# propdev.net
KiCad netlist of a schematic drawn in EAGLE
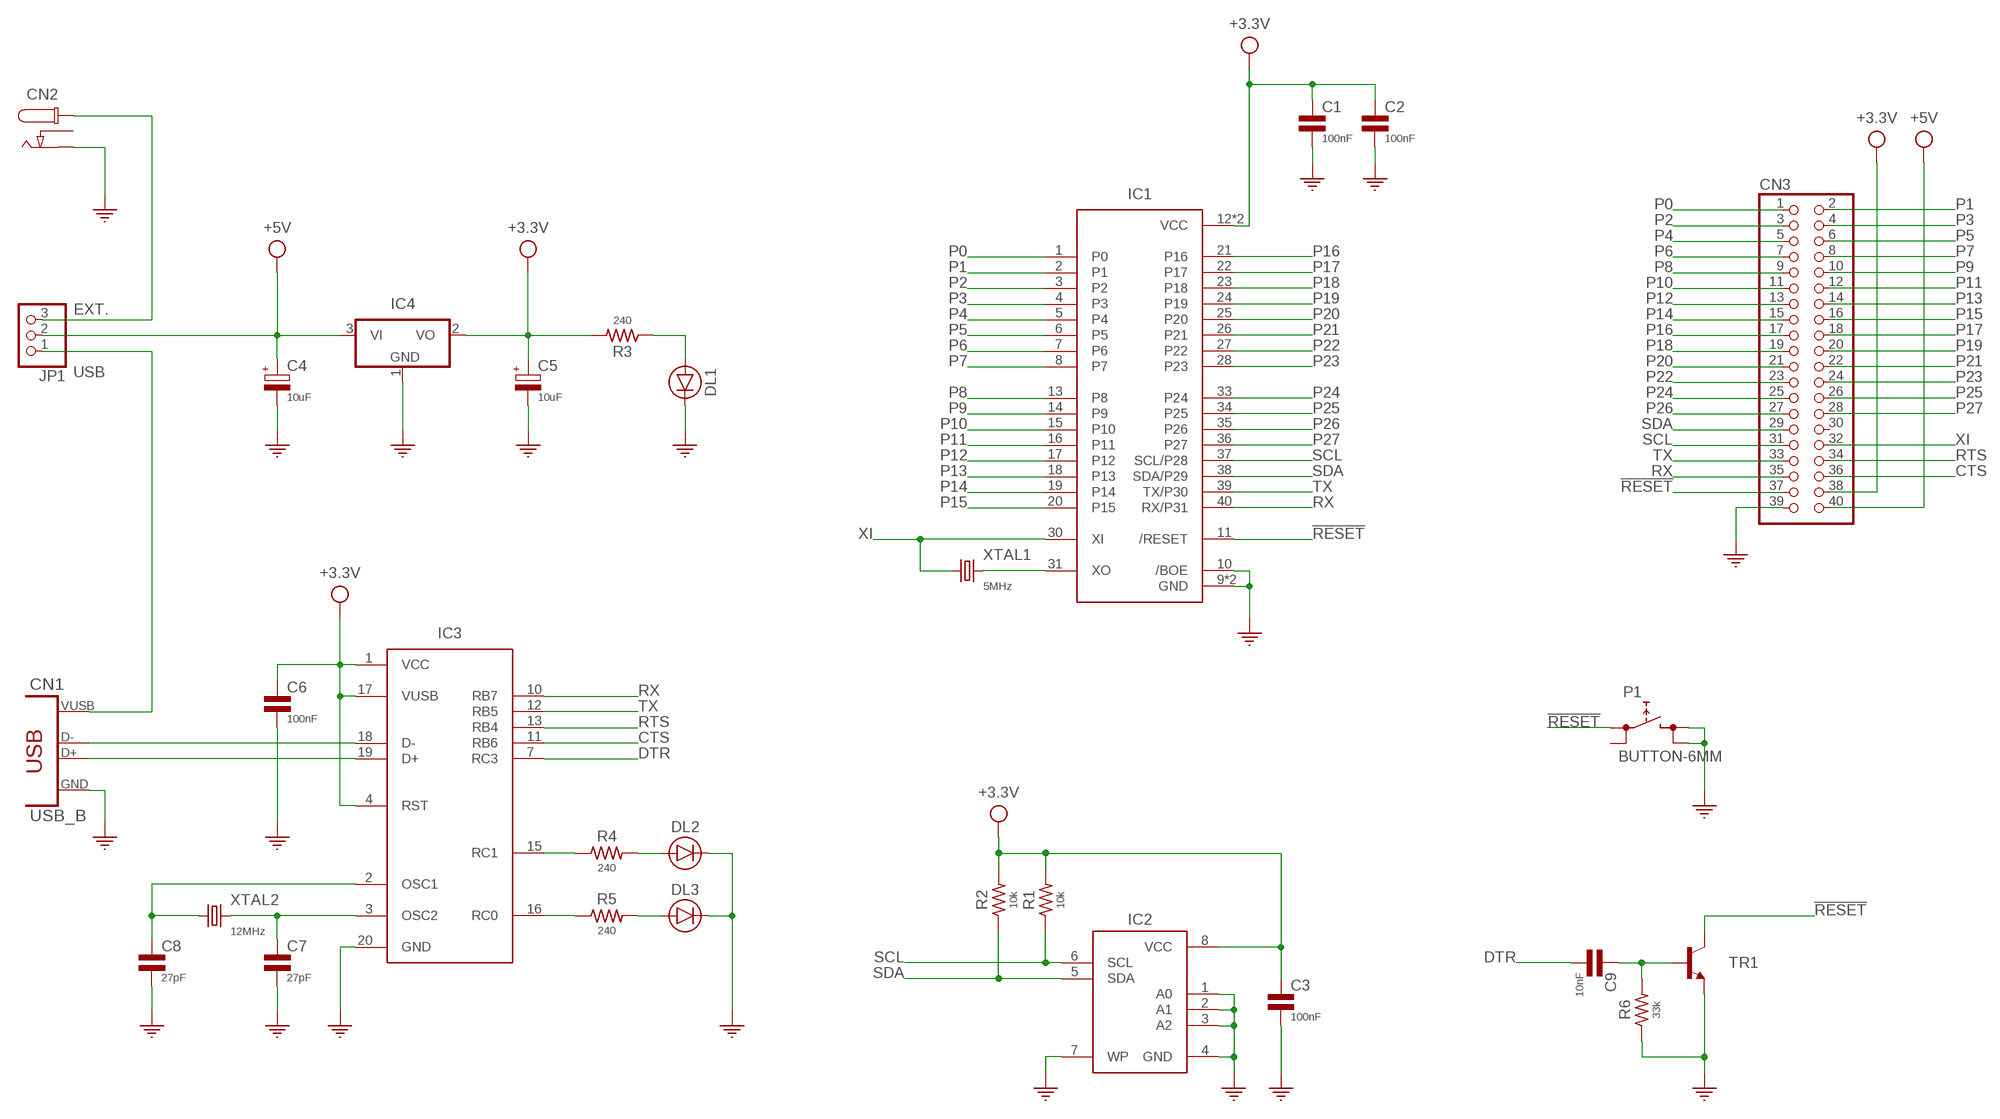
[diagram p0: schematic, sheet 1]

(export (version "E")
  (design (tool "Eeschema 10.0.6"))
  (components
    (comp (ref "C1")
      (value "100nF")
      (footprint "eagle-import:C050-025X075")
      (libsource (lib "eagle-import") (part "C"))
    )
    (comp (ref "C2")
      (value "100nF")
      (footprint "eagle-import:C050-025X075")
      (libsource (lib "eagle-import") (part "C"))
    )
    (comp (ref "C3")
      (value "100nF")
      (footprint "eagle-import:C050-025X075")
      (libsource (lib "eagle-import") (part "C"))
    )
    (comp (ref "C4")
      (value "10uF")
      (footprint "eagle-import:E2,5-6")
      (libsource (lib "eagle-import") (part "CP-2.5-6"))
    )
    (comp (ref "C5")
      (value "10uF")
      (footprint "eagle-import:E2,5-6")
      (libsource (lib "eagle-import") (part "CP-2.5-6"))
    )
    (comp (ref "C6")
      (value "100nF")
      (footprint "eagle-import:C050-025X075")
      (libsource (lib "eagle-import") (part "C"))
    )
    (comp (ref "C7")
      (value "27pF")
      (footprint "eagle-import:C050-025X075")
      (libsource (lib "eagle-import") (part "C"))
    )
    (comp (ref "C8")
      (value "27pF")
      (footprint "eagle-import:C050-025X075")
      (libsource (lib "eagle-import") (part "C"))
    )
    (comp (ref "C9")
      (value "10nF")
      (footprint "eagle-import:C050-025X075")
      (libsource (lib "eagle-import") (part "C"))
    )
    (comp (ref "CN1")
      (value "USB_B")
      (footprint "eagle-import:USB-B")
      (libsource (lib "eagle-import") (part "USB_B"))
    )
    (comp (ref "CN2")
      (value "DC_JACK")
      (footprint "eagle-import:PJ-102A")
      (libsource (lib "eagle-import") (part "DC_JACK"))
    )
    (comp (ref "CN3")
      (value "PINHD-2X20B")
      (footprint "eagle-import:2X20B")
      (libsource (lib "eagle-import") (part "PINHD-2X20B"))
    )
    (comp (ref "DL1")
      (value "LED-3MM")
      (footprint "eagle-import:LED3MM")
      (libsource (lib "eagle-import") (part "LED-3MM"))
    )
    (comp (ref "DL2")
      (value "LED-3MM")
      (footprint "eagle-import:LED3MM")
      (libsource (lib "eagle-import") (part "LED-3MM"))
    )
    (comp (ref "DL3")
      (value "LED-3MM")
      (footprint "eagle-import:LED3MM")
      (libsource (lib "eagle-import") (part "LED-3MM"))
    )
    (comp (ref "IC1")
      (value "P8X32A")
      (footprint "eagle-import:DIL40")
      (libsource (lib "eagle-import") (part "P8X32A"))
    )
    (comp (ref "IC2")
      (value "24LC512-I/P")
      (footprint "eagle-import:DIL08")
      (libsource (lib "eagle-import") (part "24LC-I/P512"))
    )
    (comp (ref "IC3")
      (value "PIC18F14K50-I/P")
      (footprint "eagle-import:DIL20")
      (libsource (lib "eagle-import") (part "PIC18F14K50-I/P"))
    )
    (comp (ref "IC4")
      (value "LM1117T-3.3")
      (footprint "eagle-import:TO220H")
      (libsource (lib "eagle-import") (part "LM1117T"))
    )
    (comp (ref "JP1")
      (value "PINHD-1X3")
      (footprint "eagle-import:1X03")
      (libsource (lib "eagle-import") (part "PINHD-1X3"))
    )
    (comp (ref "P1")
      (value "BUTTON-6MM")
      (footprint "eagle-import:TL1105")
      (libsource (lib "eagle-import") (part "BUTTON-6MM"))
    )
    (comp (ref "R1")
      (value "10k")
      (footprint "eagle-import:0207_10")
      (libsource (lib "eagle-import") (part "R-1/4W"))
    )
    (comp (ref "R2")
      (value "10k")
      (footprint "eagle-import:0207_10")
      (libsource (lib "eagle-import") (part "R-1/4W"))
    )
    (comp (ref "R3")
      (value "240")
      (footprint "eagle-import:0207_10")
      (libsource (lib "eagle-import") (part "R-1/4W"))
    )
    (comp (ref "R4")
      (value "240")
      (footprint "eagle-import:0207_10")
      (libsource (lib "eagle-import") (part "R-1/4W"))
    )
    (comp (ref "R5")
      (value "240")
      (footprint "eagle-import:0207_10")
      (libsource (lib "eagle-import") (part "R-1/4W"))
    )
    (comp (ref "R6")
      (value "33k")
      (footprint "eagle-import:0207_10")
      (libsource (lib "eagle-import") (part "R-1/4W"))
    )
    (comp (ref "TR1")
      (value "BC547")
      (footprint "eagle-import:TO92")
      (libsource (lib "eagle-import") (part "BC547"))
    )
    (comp (ref "XTAL1")
      (value "5MHz")
      (footprint "eagle-import:HC49_S")
      (libsource (lib "eagle-import") (part "CRYSTAL-HC49/S"))
    )
    (comp (ref "XTAL2")
      (value "12MHz")
      (footprint "eagle-import:HC49_S")
      (libsource (lib "eagle-import") (part "CRYSTAL-HC49/S"))
    )
  )
  (nets
    (net (code "1") (name "+3.3V") (class "Default")
      (node (ref "C1") (pin "1") (pinfunction "1_1") (pintype "passive"))
      (node (ref "C2") (pin "1") (pinfunction "1_1") (pintype "passive"))
      (node (ref "C3") (pin "1") (pinfunction "1_1") (pintype "passive"))
      (node (ref "C5") (pin "+") (pinfunction "+_+") (pintype "passive"))
      (node (ref "C6") (pin "1") (pinfunction "1_1") (pintype "passive"))
      (node (ref "CN3") (pin "38") (pinfunction "38_38") (pintype "passive"))
      (node (ref "IC1") (pin "12") (pinfunction "VCC_12") (pintype "bidirectional"))
      (node (ref "IC1") (pin "32") (pinfunction "VCC_32") (pintype "bidirectional"))
      (node (ref "IC2") (pin "8") (pinfunction "VCC_8") (pintype "bidirectional"))
      (node (ref "IC3") (pin "1") (pinfunction "VCC_1") (pintype "power_in"))
      (node (ref "IC3") (pin "17") (pinfunction "VUSB_17") (pintype "bidirectional"))
      (node (ref "IC3") (pin "4") (pinfunction "RST_4") (pintype "bidirectional"))
      (node (ref "IC4") (pin "2") (pinfunction "VO_2") (pintype "passive"))
      (node (ref "R1") (pin "2") (pinfunction "2_2") (pintype "passive"))
      (node (ref "R2") (pin "2") (pinfunction "2_2") (pintype "passive"))
      (node (ref "R3") (pin "2") (pinfunction "2_2") (pintype "passive"))
    )
    (net (code "2") (name "+5V") (class "Default")
      (node (ref "C4") (pin "+") (pinfunction "+_+") (pintype "passive"))
      (node (ref "CN3") (pin "40") (pinfunction "40_40") (pintype "passive"))
      (node (ref "IC4") (pin "3") (pinfunction "VI_3") (pintype "input"))
      (node (ref "JP1") (pin "2") (pinfunction "2_2") (pintype "passive"))
    )
    (net (code "3") (name "/CTS") (class "Default")
      (node (ref "CN3") (pin "36") (pinfunction "36_36") (pintype "passive"))
      (node (ref "IC3") (pin "11") (pinfunction "RB6_11") (pintype "bidirectional"))
    )
    (net (code "4") (name "/DTR") (class "Default")
      (node (ref "C9") (pin "2") (pinfunction "2_2") (pintype "passive"))
      (node (ref "IC3") (pin "7") (pinfunction "RC3_7") (pintype "bidirectional"))
    )
    (net (code "5") (name "/EXT.") (class "Default")
      (node (ref "CN2") (pin "P1") (pinfunction "P1_P1") (pintype "passive"))
      (node (ref "JP1") (pin "3") (pinfunction "3_3") (pintype "passive"))
    )
    (net (code "6") (name "/P0") (class "Default")
      (node (ref "CN3") (pin "1") (pinfunction "1_1") (pintype "passive"))
      (node (ref "IC1") (pin "1") (pinfunction "P0_1") (pintype "bidirectional"))
    )
    (net (code "7") (name "/P1") (class "Default")
      (node (ref "CN3") (pin "2") (pinfunction "2_2") (pintype "passive"))
      (node (ref "IC1") (pin "2") (pinfunction "P1_2") (pintype "bidirectional"))
    )
    (net (code "8") (name "/P2") (class "Default")
      (node (ref "CN3") (pin "3") (pinfunction "3_3") (pintype "passive"))
      (node (ref "IC1") (pin "3") (pinfunction "P2_3") (pintype "bidirectional"))
    )
    (net (code "9") (name "/P3") (class "Default")
      (node (ref "CN3") (pin "4") (pinfunction "4_4") (pintype "passive"))
      (node (ref "IC1") (pin "4") (pinfunction "P3_4") (pintype "bidirectional"))
    )
    (net (code "10") (name "/P4") (class "Default")
      (node (ref "CN3") (pin "5") (pinfunction "5_5") (pintype "passive"))
      (node (ref "IC1") (pin "5") (pinfunction "P4_5") (pintype "bidirectional"))
    )
    (net (code "11") (name "/P5") (class "Default")
      (node (ref "CN3") (pin "6") (pinfunction "6_6") (pintype "passive"))
      (node (ref "IC1") (pin "6") (pinfunction "P5_6") (pintype "bidirectional"))
    )
    (net (code "12") (name "/P6") (class "Default")
      (node (ref "CN3") (pin "7") (pinfunction "7_7") (pintype "passive"))
      (node (ref "IC1") (pin "7") (pinfunction "P6_7") (pintype "bidirectional"))
    )
    (net (code "13") (name "/P7") (class "Default")
      (node (ref "CN3") (pin "8") (pinfunction "8_8") (pintype "passive"))
      (node (ref "IC1") (pin "8") (pinfunction "P7_8") (pintype "bidirectional"))
    )
    (net (code "14") (name "/P8") (class "Default")
      (node (ref "CN3") (pin "9") (pinfunction "9_9") (pintype "passive"))
      (node (ref "IC1") (pin "13") (pinfunction "P8_13") (pintype "bidirectional"))
    )
    (net (code "15") (name "/P9") (class "Default")
      (node (ref "CN3") (pin "10") (pinfunction "10_10") (pintype "passive"))
      (node (ref "IC1") (pin "14") (pinfunction "P9_14") (pintype "bidirectional"))
    )
    (net (code "16") (name "/P10") (class "Default")
      (node (ref "CN3") (pin "11") (pinfunction "11_11") (pintype "passive"))
      (node (ref "IC1") (pin "15") (pinfunction "P10_15") (pintype "bidirectional"))
    )
    (net (code "17") (name "/P11") (class "Default")
      (node (ref "CN3") (pin "12") (pinfunction "12_12") (pintype "passive"))
      (node (ref "IC1") (pin "16") (pinfunction "P11_16") (pintype "bidirectional"))
    )
    (net (code "18") (name "/P12") (class "Default")
      (node (ref "CN3") (pin "13") (pinfunction "13_13") (pintype "passive"))
      (node (ref "IC1") (pin "17") (pinfunction "P12_17") (pintype "bidirectional"))
    )
    (net (code "19") (name "/P13") (class "Default")
      (node (ref "CN3") (pin "14") (pinfunction "14_14") (pintype "passive"))
      (node (ref "IC1") (pin "18") (pinfunction "P13_18") (pintype "bidirectional"))
    )
    (net (code "20") (name "/P14") (class "Default")
      (node (ref "CN3") (pin "15") (pinfunction "15_15") (pintype "passive"))
      (node (ref "IC1") (pin "19") (pinfunction "P14_19") (pintype "bidirectional"))
    )
    (net (code "21") (name "/P15") (class "Default")
      (node (ref "CN3") (pin "16") (pinfunction "16_16") (pintype "passive"))
      (node (ref "IC1") (pin "20") (pinfunction "P15_20") (pintype "bidirectional"))
    )
    (net (code "22") (name "/P16") (class "Default")
      (node (ref "CN3") (pin "17") (pinfunction "17_17") (pintype "passive"))
      (node (ref "IC1") (pin "21") (pinfunction "P16_21") (pintype "bidirectional"))
    )
    (net (code "23") (name "/P17") (class "Default")
      (node (ref "CN3") (pin "18") (pinfunction "18_18") (pintype "passive"))
      (node (ref "IC1") (pin "22") (pinfunction "P17_22") (pintype "bidirectional"))
    )
    (net (code "24") (name "/P18") (class "Default")
      (node (ref "CN3") (pin "19") (pinfunction "19_19") (pintype "passive"))
      (node (ref "IC1") (pin "23") (pinfunction "P18_23") (pintype "bidirectional"))
    )
    (net (code "25") (name "/P19") (class "Default")
      (node (ref "CN3") (pin "20") (pinfunction "20_20") (pintype "passive"))
      (node (ref "IC1") (pin "24") (pinfunction "P19_24") (pintype "bidirectional"))
    )
    (net (code "26") (name "/P20") (class "Default")
      (node (ref "CN3") (pin "21") (pinfunction "21_21") (pintype "passive"))
      (node (ref "IC1") (pin "25") (pinfunction "P20_25") (pintype "bidirectional"))
    )
    (net (code "27") (name "/P21") (class "Default")
      (node (ref "CN3") (pin "22") (pinfunction "22_22") (pintype "passive"))
      (node (ref "IC1") (pin "26") (pinfunction "P21_26") (pintype "bidirectional"))
    )
    (net (code "28") (name "/P22") (class "Default")
      (node (ref "CN3") (pin "23") (pinfunction "23_23") (pintype "passive"))
      (node (ref "IC1") (pin "27") (pinfunction "P22_27") (pintype "bidirectional"))
    )
    (net (code "29") (name "/P23") (class "Default")
      (node (ref "CN3") (pin "24") (pinfunction "24_24") (pintype "passive"))
      (node (ref "IC1") (pin "28") (pinfunction "P23_28") (pintype "bidirectional"))
    )
    (net (code "30") (name "/P24") (class "Default")
      (node (ref "CN3") (pin "25") (pinfunction "25_25") (pintype "passive"))
      (node (ref "IC1") (pin "33") (pinfunction "P24_33") (pintype "bidirectional"))
    )
    (net (code "31") (name "/P25") (class "Default")
      (node (ref "CN3") (pin "26") (pinfunction "26_26") (pintype "passive"))
      (node (ref "IC1") (pin "34") (pinfunction "P25_34") (pintype "bidirectional"))
    )
    (net (code "32") (name "/P26") (class "Default")
      (node (ref "CN3") (pin "27") (pinfunction "27_27") (pintype "passive"))
      (node (ref "IC1") (pin "35") (pinfunction "P26_35") (pintype "bidirectional"))
    )
    (net (code "33") (name "/P27") (class "Default")
      (node (ref "CN3") (pin "28") (pinfunction "28_28") (pintype "passive"))
      (node (ref "IC1") (pin "36") (pinfunction "P27_36") (pintype "bidirectional"))
    )
    (net (code "34") (name "/RTS") (class "Default")
      (node (ref "CN3") (pin "34") (pinfunction "34_34") (pintype "passive"))
      (node (ref "IC3") (pin "13") (pinfunction "RB4_13") (pintype "bidirectional"))
    )
    (net (code "35") (name "/RX") (class "Default")
      (node (ref "CN3") (pin "35") (pinfunction "35_35") (pintype "passive"))
      (node (ref "IC1") (pin "40") (pinfunction "RX/P31_40") (pintype "bidirectional"))
      (node (ref "IC3") (pin "10") (pinfunction "RB7_10") (pintype "bidirectional"))
    )
    (net (code "36") (name "/SCL") (class "Default")
      (node (ref "CN3") (pin "31") (pinfunction "31_31") (pintype "passive"))
      (node (ref "IC1") (pin "37") (pinfunction "SCL/P28_37") (pintype "bidirectional"))
      (node (ref "IC2") (pin "6") (pinfunction "SCL_6") (pintype "bidirectional"))
      (node (ref "R1") (pin "1") (pinfunction "1_1") (pintype "passive"))
    )
    (net (code "37") (name "/SDA") (class "Default")
      (node (ref "CN3") (pin "29") (pinfunction "29_29") (pintype "passive"))
      (node (ref "IC1") (pin "38") (pinfunction "SDA/P29_38") (pintype "bidirectional"))
      (node (ref "IC2") (pin "5") (pinfunction "SDA_5") (pintype "bidirectional"))
      (node (ref "R2") (pin "1") (pinfunction "1_1") (pintype "passive"))
    )
    (net (code "38") (name "/TX") (class "Default")
      (node (ref "CN3") (pin "33") (pinfunction "33_33") (pintype "passive"))
      (node (ref "IC1") (pin "39") (pinfunction "TX/P30_39") (pintype "bidirectional"))
      (node (ref "IC3") (pin "12") (pinfunction "RB5_12") (pintype "bidirectional"))
    )
    (net (code "39") (name "/USB") (class "Default")
      (node (ref "CN1") (pin "1") (pinfunction "VUSB_1") (pintype "power_in"))
      (node (ref "JP1") (pin "1") (pinfunction "1_1") (pintype "passive"))
    )
    (net (code "40") (name "/XI") (class "Default")
      (node (ref "CN3") (pin "32") (pinfunction "32_32") (pintype "passive"))
      (node (ref "IC1") (pin "30") (pinfunction "XI_30") (pintype "open_collector"))
      (node (ref "XTAL1") (pin "1") (pinfunction "1_1") (pintype "passive"))
    )
    (net (code "41") (name "/~{RESET}") (class "Default")
      (node (ref "CN3") (pin "37") (pinfunction "37_37") (pintype "passive"))
      (node (ref "IC1") (pin "11") (pinfunction "/RESET_11") (pintype "bidirectional"))
      (node (ref "P1") (pin "1") (pinfunction "0_1") (pintype "passive"))
      (node (ref "TR1") (pin "3") (pinfunction "C_3") (pintype "passive"))
    )
    (net (code "42") (name "GND") (class "Default")
      (node (ref "C1") (pin "2") (pinfunction "2_2") (pintype "passive"))
      (node (ref "C2") (pin "2") (pinfunction "2_2") (pintype "passive"))
      (node (ref "C3") (pin "2") (pinfunction "2_2") (pintype "passive"))
      (node (ref "C4") (pin "-") (pinfunction "-_-") (pintype "passive"))
      (node (ref "C5") (pin "-") (pinfunction "-_-") (pintype "passive"))
      (node (ref "C6") (pin "2") (pinfunction "2_2") (pintype "passive"))
      (node (ref "C7") (pin "2") (pinfunction "2_2") (pintype "passive"))
      (node (ref "C8") (pin "2") (pinfunction "2_2") (pintype "passive"))
      (node (ref "CN1") (pin "4") (pinfunction "GND_4") (pintype "power_in"))
      (node (ref "CN2") (pin "P3") (pinfunction "P2_P3") (pintype "passive"))
      (node (ref "CN3") (pin "39") (pinfunction "39_39") (pintype "passive"))
      (node (ref "DL1") (pin "K") (pinfunction "C_K") (pintype "passive"))
      (node (ref "DL2") (pin "K") (pinfunction "C_K") (pintype "passive"))
      (node (ref "DL3") (pin "K") (pinfunction "C_K") (pintype "passive"))
      (node (ref "IC1") (pin "10") (pinfunction "/BOE_10") (pintype "input"))
      (node (ref "IC1") (pin "29") (pinfunction "GND_29") (pintype "bidirectional"))
      (node (ref "IC1") (pin "9") (pinfunction "GND_9") (pintype "bidirectional"))
      (node (ref "IC2") (pin "1") (pinfunction "A0_1") (pintype "input"))
      (node (ref "IC2") (pin "2") (pinfunction "A1_2") (pintype "input"))
      (node (ref "IC2") (pin "3") (pinfunction "A2_3") (pintype "input"))
      (node (ref "IC2") (pin "4") (pinfunction "GND_4") (pintype "bidirectional"))
      (node (ref "IC2") (pin "7") (pinfunction "WP_7") (pintype "input"))
      (node (ref "IC3") (pin "20") (pinfunction "GND_20") (pintype "power_in"))
      (node (ref "IC4") (pin "1") (pinfunction "GND_1") (pintype "passive"))
      (node (ref "P1") (pin "2") (pinfunction "1_2") (pintype "passive"))
      (node (ref "P1") (pin "4") (pinfunction "1_4") (pintype "passive"))
      (node (ref "R6") (pin "1") (pinfunction "1_1") (pintype "passive"))
      (node (ref "TR1") (pin "1") (pinfunction "E_1") (pintype "passive"))
    )
    (net (code "43") (name "Net-(CN1-D+)") (class "Default")
      (node (ref "CN1") (pin "3") (pinfunction "D+_3") (pintype "bidirectional"))
      (node (ref "IC3") (pin "19") (pinfunction "D+_19") (pintype "bidirectional"))
    )
    (net (code "44") (name "Net-(CN1-D-)") (class "Default")
      (node (ref "CN1") (pin "2") (pinfunction "D-_2") (pintype "bidirectional"))
      (node (ref "IC3") (pin "18") (pinfunction "D-_18") (pintype "bidirectional"))
    )
    (net (code "45") (name "Net-(DL1-PadA)") (class "Default")
      (node (ref "DL1") (pin "A") (pinfunction "A_A") (pintype "passive"))
      (node (ref "R3") (pin "1") (pinfunction "1_1") (pintype "passive"))
    )
    (net (code "46") (name "Net-(DL2-PadA)") (class "Default")
      (node (ref "DL2") (pin "A") (pinfunction "A_A") (pintype "passive"))
      (node (ref "R4") (pin "2") (pinfunction "2_2") (pintype "passive"))
    )
    (net (code "47") (name "Net-(DL3-PadA)") (class "Default")
      (node (ref "DL3") (pin "A") (pinfunction "A_A") (pintype "passive"))
      (node (ref "R5") (pin "2") (pinfunction "2_2") (pintype "passive"))
    )
    (net (code "48") (name "Net-(IC1-XO)") (class "Default")
      (node (ref "IC1") (pin "31") (pinfunction "XO_31") (pintype "open_collector"))
      (node (ref "XTAL1") (pin "2") (pinfunction "2_2") (pintype "passive"))
    )
    (net (code "49") (name "Net-(IC3-OSC1)") (class "Default")
      (node (ref "C8") (pin "1") (pinfunction "1_1") (pintype "passive"))
      (node (ref "IC3") (pin "2") (pinfunction "OSC1_2") (pintype "bidirectional"))
      (node (ref "XTAL2") (pin "1") (pinfunction "1_1") (pintype "passive"))
    )
    (net (code "50") (name "Net-(IC3-OSC2)") (class "Default")
      (node (ref "C7") (pin "1") (pinfunction "1_1") (pintype "passive"))
      (node (ref "IC3") (pin "3") (pinfunction "OSC2_3") (pintype "bidirectional"))
      (node (ref "XTAL2") (pin "2") (pinfunction "2_2") (pintype "passive"))
    )
    (net (code "51") (name "Net-(IC3-RC0)") (class "Default")
      (node (ref "IC3") (pin "16") (pinfunction "RC0_16") (pintype "bidirectional"))
      (node (ref "R5") (pin "1") (pinfunction "1_1") (pintype "passive"))
    )
    (net (code "52") (name "Net-(IC3-RC1)") (class "Default")
      (node (ref "IC3") (pin "15") (pinfunction "RC1_15") (pintype "bidirectional"))
      (node (ref "R4") (pin "1") (pinfunction "1_1") (pintype "passive"))
    )
    (net (code "53") (name "Net-(TR1-B)") (class "Default")
      (node (ref "C9") (pin "1") (pinfunction "1_1") (pintype "passive"))
      (node (ref "R6") (pin "2") (pinfunction "2_2") (pintype "passive"))
      (node (ref "TR1") (pin "2") (pinfunction "B_2") (pintype "passive"))
    )
    (net (code "54") (name "unconnected-(CN2-P3-PadP2)") (class "Default")
      (node (ref "CN2") (pin "P2") (pinfunction "P3_P2") (pintype "passive"))
    )
    (net (code "55") (name "unconnected-(CN3-Pad30)") (class "Default")
      (node (ref "CN3") (pin "30") (pinfunction "30_30") (pintype "passive"))
    )
    (net (code "56") (name "unconnected-(P1-0-Pad3)") (class "Default")
      (node (ref "P1") (pin "3") (pinfunction "0_3") (pintype "passive"))
    )
  )
)
